# 01-AD9546-Main.net
KiCad netlist of a schematic drawn in Altium Designer
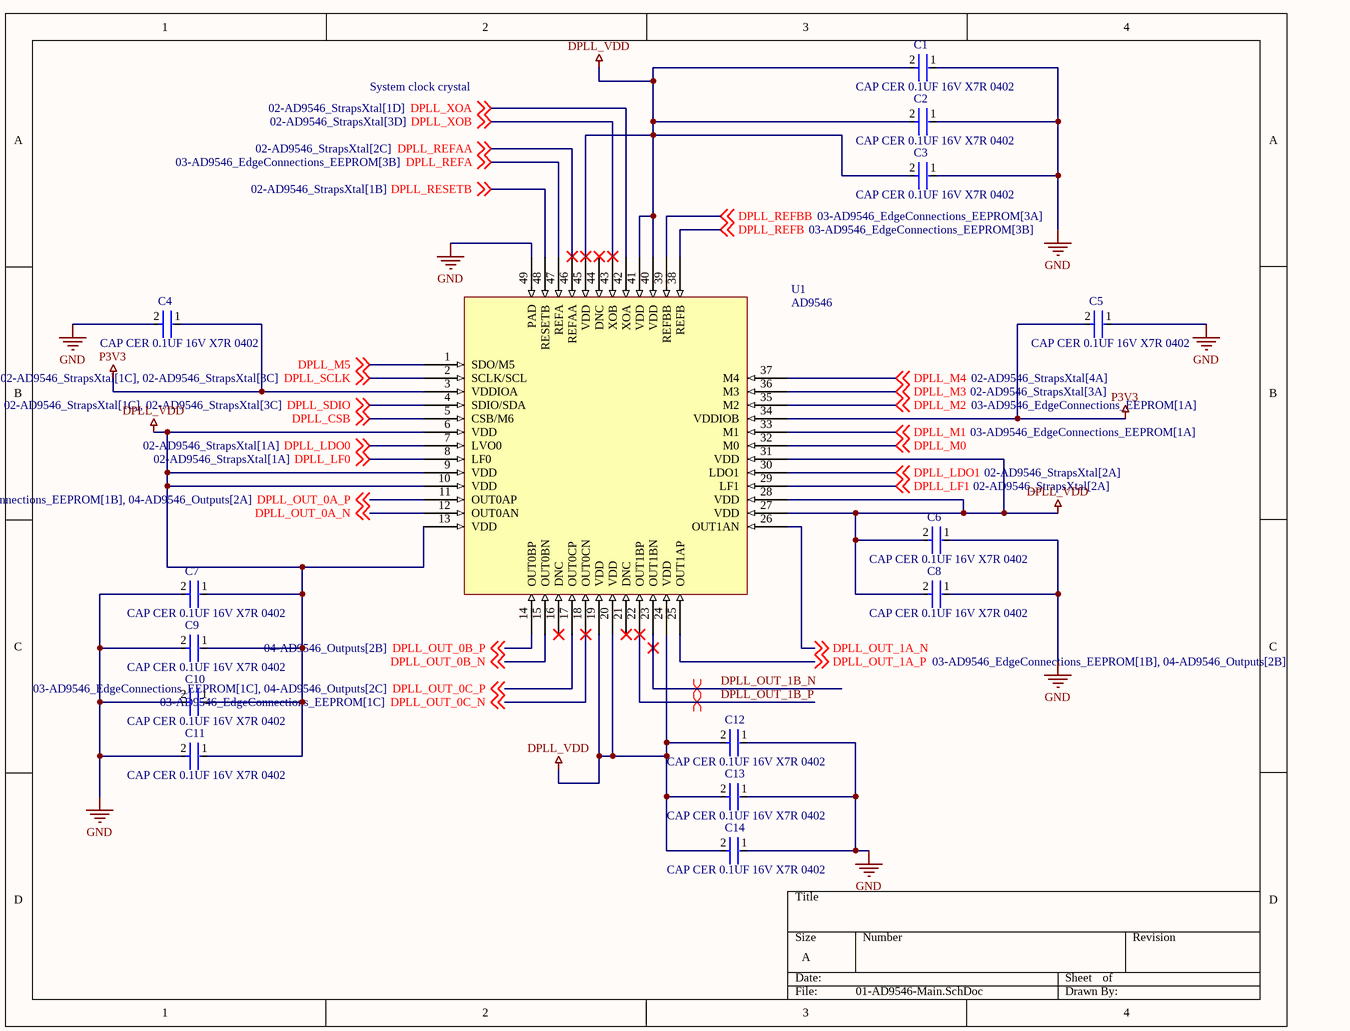
[diagram p0: 01-AD9546-Main.SchDoc]

(export (version "E")
  (design (tool "Eeschema 10.0.6"))
  (components
    (comp (ref "C1")
      (value "GRM155R71C104KA88D")
      (footprint "FP-GRM15-MFG")
      (description "CAP CER 0.1UF 16V X7R 0402")
      (fields
        (field (name "TOLERANCE") "10%")
        (field (name "OCTOPART") "https://octopart.com/grm155r71c104ka88d-murata-196880")
        (field (name "DIGIKEY DESCRIPTION") "CAP CER 0.1UF 16V X7R 0402")
      )
      (libsource (lib "Altium Content Vault") (part "236180d848d6139a670b325ea6854c9"))
    )
    (comp (ref "C2")
      (value "GRM155R71C104KA88D")
      (footprint "FP-GRM15-MFG")
      (description "CAP CER 0.1UF 16V X7R 0402")
      (fields
        (field (name "TOLERANCE") "10%")
        (field (name "OCTOPART") "https://octopart.com/grm155r71c104ka88d-murata-196880")
        (field (name "DIGIKEY DESCRIPTION") "CAP CER 0.1UF 16V X7R 0402")
      )
      (libsource (lib "Altium Content Vault") (part "236180d848d6139a670b325ea6854c9"))
    )
    (comp (ref "C3")
      (value "GRM155R71C104KA88D")
      (footprint "FP-GRM15-MFG")
      (description "CAP CER 0.1UF 16V X7R 0402")
      (fields
        (field (name "TOLERANCE") "10%")
        (field (name "OCTOPART") "https://octopart.com/grm155r71c104ka88d-murata-196880")
        (field (name "DIGIKEY DESCRIPTION") "CAP CER 0.1UF 16V X7R 0402")
      )
      (libsource (lib "Altium Content Vault") (part "236180d848d6139a670b325ea6854c9"))
    )
    (comp (ref "C4")
      (value "GRM155R71C104KA88D")
      (footprint "FP-GRM15-MFG")
      (description "CAP CER 0.1UF 16V X7R 0402")
      (fields
        (field (name "TOLERANCE") "10%")
        (field (name "OCTOPART") "https://octopart.com/grm155r71c104ka88d-murata-196880")
        (field (name "DIGIKEY DESCRIPTION") "CAP CER 0.1UF 16V X7R 0402")
      )
      (libsource (lib "Altium Content Vault") (part "236180d848d6139a670b325ea6854c9"))
    )
    (comp (ref "C5")
      (value "GRM155R71C104KA88D")
      (footprint "FP-GRM15-MFG")
      (description "CAP CER 0.1UF 16V X7R 0402")
      (fields
        (field (name "TOLERANCE") "10%")
        (field (name "OCTOPART") "https://octopart.com/grm155r71c104ka88d-murata-196880")
        (field (name "DIGIKEY DESCRIPTION") "CAP CER 0.1UF 16V X7R 0402")
      )
      (libsource (lib "Altium Content Vault") (part "236180d848d6139a670b325ea6854c9"))
    )
    (comp (ref "C6")
      (value "GRM155R71C104KA88D")
      (footprint "FP-GRM15-MFG")
      (description "CAP CER 0.1UF 16V X7R 0402")
      (fields
        (field (name "TOLERANCE") "10%")
        (field (name "OCTOPART") "https://octopart.com/grm155r71c104ka88d-murata-196880")
        (field (name "DIGIKEY DESCRIPTION") "CAP CER 0.1UF 16V X7R 0402")
      )
      (libsource (lib "Altium Content Vault") (part "236180d848d6139a670b325ea6854c9"))
    )
    (comp (ref "C7")
      (value "GRM155R71C104KA88D")
      (footprint "FP-GRM15-MFG")
      (description "CAP CER 0.1UF 16V X7R 0402")
      (fields
        (field (name "TOLERANCE") "10%")
        (field (name "OCTOPART") "https://octopart.com/grm155r71c104ka88d-murata-196880")
        (field (name "DIGIKEY DESCRIPTION") "CAP CER 0.1UF 16V X7R 0402")
      )
      (libsource (lib "Altium Content Vault") (part "236180d848d6139a670b325ea6854c9"))
    )
    (comp (ref "C8")
      (value "GRM155R71C104KA88D")
      (footprint "FP-GRM15-MFG")
      (description "CAP CER 0.1UF 16V X7R 0402")
      (fields
        (field (name "TOLERANCE") "10%")
        (field (name "OCTOPART") "https://octopart.com/grm155r71c104ka88d-murata-196880")
        (field (name "DIGIKEY DESCRIPTION") "CAP CER 0.1UF 16V X7R 0402")
      )
      (libsource (lib "Altium Content Vault") (part "236180d848d6139a670b325ea6854c9"))
    )
    (comp (ref "C9")
      (value "GRM155R71C104KA88D")
      (footprint "FP-GRM15-MFG")
      (description "CAP CER 0.1UF 16V X7R 0402")
      (fields
        (field (name "TOLERANCE") "10%")
        (field (name "OCTOPART") "https://octopart.com/grm155r71c104ka88d-murata-196880")
        (field (name "DIGIKEY DESCRIPTION") "CAP CER 0.1UF 16V X7R 0402")
      )
      (libsource (lib "Altium Content Vault") (part "236180d848d6139a670b325ea6854c9"))
    )
    (comp (ref "C10")
      (value "GRM155R71C104KA88D")
      (footprint "FP-GRM15-MFG")
      (description "CAP CER 0.1UF 16V X7R 0402")
      (fields
        (field (name "TOLERANCE") "10%")
        (field (name "OCTOPART") "https://octopart.com/grm155r71c104ka88d-murata-196880")
        (field (name "DIGIKEY DESCRIPTION") "CAP CER 0.1UF 16V X7R 0402")
      )
      (libsource (lib "Altium Content Vault") (part "236180d848d6139a670b325ea6854c9"))
    )
    (comp (ref "C11")
      (value "GRM155R71C104KA88D")
      (footprint "FP-GRM15-MFG")
      (description "CAP CER 0.1UF 16V X7R 0402")
      (fields
        (field (name "TOLERANCE") "10%")
        (field (name "OCTOPART") "https://octopart.com/grm155r71c104ka88d-murata-196880")
        (field (name "DIGIKEY DESCRIPTION") "CAP CER 0.1UF 16V X7R 0402")
      )
      (libsource (lib "Altium Content Vault") (part "236180d848d6139a670b325ea6854c9"))
    )
    (comp (ref "C12")
      (value "GRM155R71C104KA88D")
      (footprint "FP-GRM15-MFG")
      (description "CAP CER 0.1UF 16V X7R 0402")
      (fields
        (field (name "TOLERANCE") "10%")
        (field (name "OCTOPART") "https://octopart.com/grm155r71c104ka88d-murata-196880")
        (field (name "DIGIKEY DESCRIPTION") "CAP CER 0.1UF 16V X7R 0402")
      )
      (libsource (lib "Altium Content Vault") (part "236180d848d6139a670b325ea6854c9"))
    )
    (comp (ref "C13")
      (value "GRM155R71C104KA88D")
      (footprint "FP-GRM15-MFG")
      (description "CAP CER 0.1UF 16V X7R 0402")
      (fields
        (field (name "TOLERANCE") "10%")
        (field (name "OCTOPART") "https://octopart.com/grm155r71c104ka88d-murata-196880")
        (field (name "DIGIKEY DESCRIPTION") "CAP CER 0.1UF 16V X7R 0402")
      )
      (libsource (lib "Altium Content Vault") (part "236180d848d6139a670b325ea6854c9"))
    )
    (comp (ref "C14")
      (value "GRM155R71C104KA88D")
      (footprint "FP-GRM15-MFG")
      (description "CAP CER 0.1UF 16V X7R 0402")
      (fields
        (field (name "TOLERANCE") "10%")
        (field (name "OCTOPART") "https://octopart.com/grm155r71c104ka88d-murata-196880")
        (field (name "DIGIKEY DESCRIPTION") "CAP CER 0.1UF 16V X7R 0402")
      )
      (libsource (lib "Altium Content Vault") (part "236180d848d6139a670b325ea6854c9"))
    )
    (comp (ref "U1") (value "AD9546") (footprint "AD9546") (libsource (lib "TimeStick_Lib") (part "AD9546")))
  )
  (nets
    (net (code "1") (name "/DPLL_OUT_1B_N") (class "Default")
      (node (ref "U1") (pin "23") (pinfunction "OUT1BN_23") (pintype "input"))
    )
    (net (code "2") (name "/DPLL_OUT_1B_P") (class "Default")
      (node (ref "U1") (pin "22") (pinfunction "OUT1BP_22") (pintype "input+no_connect"))
    )
    (net (code "3") (name "DPLL_CSB") (class "Default")
      (node (ref "U1") (pin "5") (pinfunction "CSB/M6_5") (pintype "input"))
    )
    (net (code "4") (name "DPLL_LDO0") (class "Default")
      (node (ref "U1") (pin "7") (pinfunction "LVO0_7") (pintype "input"))
    )
    (net (code "5") (name "DPLL_LDO1") (class "Default")
      (node (ref "U1") (pin "30") (pinfunction "LDO1_30") (pintype "input"))
    )
    (net (code "6") (name "DPLL_LF0") (class "Default")
      (node (ref "U1") (pin "8") (pinfunction "LF0_8") (pintype "input"))
    )
    (net (code "7") (name "DPLL_LF1") (class "Default")
      (node (ref "U1") (pin "29") (pinfunction "LF1_29") (pintype "input"))
    )
    (net (code "8") (name "DPLL_M0") (class "Default")
      (node (ref "U1") (pin "32") (pinfunction "M0_32") (pintype "input"))
    )
    (net (code "9") (name "DPLL_M1") (class "Default")
      (node (ref "U1") (pin "33") (pinfunction "M1_33") (pintype "input"))
    )
    (net (code "10") (name "DPLL_M2") (class "Default")
      (node (ref "U1") (pin "35") (pinfunction "M2_35") (pintype "input"))
    )
    (net (code "11") (name "DPLL_M3") (class "Default")
      (node (ref "U1") (pin "36") (pinfunction "M3_36") (pintype "input"))
    )
    (net (code "12") (name "DPLL_M4") (class "Default")
      (node (ref "U1") (pin "37") (pinfunction "M4_37") (pintype "input"))
    )
    (net (code "13") (name "DPLL_M5") (class "Default")
      (node (ref "U1") (pin "1") (pinfunction "SDO/M5_1") (pintype "input"))
    )
    (net (code "14") (name "DPLL_OUT_0A_N") (class "Default")
      (node (ref "U1") (pin "12") (pinfunction "OUT0AN_12") (pintype "input"))
    )
    (net (code "15") (name "DPLL_OUT_0A_P") (class "Default")
      (node (ref "U1") (pin "11") (pinfunction "OUT0AP_11") (pintype "input"))
    )
    (net (code "16") (name "DPLL_OUT_0B_N") (class "Default")
      (node (ref "U1") (pin "15") (pinfunction "OUT0BN_15") (pintype "input"))
    )
    (net (code "17") (name "DPLL_OUT_0B_P") (class "Default")
      (node (ref "U1") (pin "14") (pinfunction "OUT0BP_14") (pintype "input"))
    )
    (net (code "18") (name "DPLL_OUT_0C_N") (class "Default")
      (node (ref "U1") (pin "18") (pinfunction "OUT0CN_18") (pintype "input"))
    )
    (net (code "19") (name "DPLL_OUT_0C_P") (class "Default")
      (node (ref "U1") (pin "17") (pinfunction "OUT0CP_17") (pintype "input"))
    )
    (net (code "20") (name "DPLL_OUT_1A_N") (class "Default")
      (node (ref "U1") (pin "26") (pinfunction "OUT1AN_26") (pintype "input"))
    )
    (net (code "21") (name "DPLL_OUT_1A_P") (class "Default")
      (node (ref "U1") (pin "25") (pinfunction "OUT1AP_25") (pintype "input"))
    )
    (net (code "22") (name "DPLL_REFA") (class "Default")
      (node (ref "U1") (pin "47") (pinfunction "REFA_47") (pintype "input"))
    )
    (net (code "23") (name "DPLL_REFAA") (class "Default")
      (node (ref "U1") (pin "46") (pinfunction "REFAA_46") (pintype "input"))
    )
    (net (code "24") (name "DPLL_REFB") (class "Default")
      (node (ref "U1") (pin "38") (pinfunction "REFB_38") (pintype "input"))
    )
    (net (code "25") (name "DPLL_REFBB") (class "Default")
      (node (ref "U1") (pin "39") (pinfunction "REFBB_39") (pintype "input"))
    )
    (net (code "26") (name "DPLL_RESETB") (class "Default")
      (node (ref "U1") (pin "48") (pinfunction "RESETB_48") (pintype "input"))
    )
    (net (code "27") (name "DPLL_SCLK") (class "Default")
      (node (ref "U1") (pin "2") (pinfunction "SCLK/SCL_2") (pintype "input"))
    )
    (net (code "28") (name "DPLL_SDIO") (class "Default")
      (node (ref "U1") (pin "4") (pinfunction "SDIO/SDA_4") (pintype "input"))
    )
    (net (code "29") (name "DPLL_VDD") (class "Default")
      (node (ref "C1") (pin "2") (pinfunction "2_2") (pintype "passive"))
      (node (ref "C10") (pin "1") (pinfunction "1_1") (pintype "passive"))
      (node (ref "C11") (pin "1") (pinfunction "1_1") (pintype "passive"))
      (node (ref "C12") (pin "2") (pinfunction "2_2") (pintype "passive"))
      (node (ref "C13") (pin "2") (pinfunction "2_2") (pintype "passive"))
      (node (ref "C14") (pin "2") (pinfunction "2_2") (pintype "passive"))
      (node (ref "C2") (pin "2") (pinfunction "2_2") (pintype "passive"))
      (node (ref "C3") (pin "2") (pinfunction "2_2") (pintype "passive"))
      (node (ref "C6") (pin "2") (pinfunction "2_2") (pintype "passive"))
      (node (ref "C7") (pin "1") (pinfunction "1_1") (pintype "passive"))
      (node (ref "C8") (pin "2") (pinfunction "2_2") (pintype "passive"))
      (node (ref "C9") (pin "1") (pinfunction "1_1") (pintype "passive"))
      (node (ref "U1") (pin "10") (pinfunction "VDD_10") (pintype "input"))
      (node (ref "U1") (pin "13") (pinfunction "VDD_13") (pintype "input"))
      (node (ref "U1") (pin "19") (pinfunction "VDD_19") (pintype "input"))
      (node (ref "U1") (pin "20") (pinfunction "VDD_20") (pintype "input"))
      (node (ref "U1") (pin "24") (pinfunction "VDD_24") (pintype "input"))
      (node (ref "U1") (pin "27") (pinfunction "VDD_27") (pintype "input"))
      (node (ref "U1") (pin "28") (pinfunction "VDD_28") (pintype "input"))
      (node (ref "U1") (pin "31") (pinfunction "VDD_31") (pintype "input"))
      (node (ref "U1") (pin "40") (pinfunction "VDD_40") (pintype "input"))
      (node (ref "U1") (pin "41") (pinfunction "VDD_41") (pintype "input"))
      (node (ref "U1") (pin "45") (pinfunction "VDD_45") (pintype "input"))
      (node (ref "U1") (pin "6") (pinfunction "VDD_6") (pintype "input"))
      (node (ref "U1") (pin "9") (pinfunction "VDD_9") (pintype "input"))
    )
    (net (code "30") (name "DPLL_XOA") (class "Default")
      (node (ref "U1") (pin "42") (pinfunction "XOA_42") (pintype "input"))
    )
    (net (code "31") (name "DPLL_XOB") (class "Default")
      (node (ref "U1") (pin "43") (pinfunction "XOB_43") (pintype "input"))
    )
    (net (code "32") (name "GND") (class "Default")
      (node (ref "C1") (pin "1") (pinfunction "1_1") (pintype "passive"))
      (node (ref "C10") (pin "2") (pinfunction "2_2") (pintype "passive"))
      (node (ref "C11") (pin "2") (pinfunction "2_2") (pintype "passive"))
      (node (ref "C12") (pin "1") (pinfunction "1_1") (pintype "passive"))
      (node (ref "C13") (pin "1") (pinfunction "1_1") (pintype "passive"))
      (node (ref "C14") (pin "1") (pinfunction "1_1") (pintype "passive"))
      (node (ref "C2") (pin "1") (pinfunction "1_1") (pintype "passive"))
      (node (ref "C3") (pin "1") (pinfunction "1_1") (pintype "passive"))
      (node (ref "C4") (pin "2") (pinfunction "2_2") (pintype "passive"))
      (node (ref "C5") (pin "1") (pinfunction "1_1") (pintype "passive"))
      (node (ref "C6") (pin "1") (pinfunction "1_1") (pintype "passive"))
      (node (ref "C7") (pin "2") (pinfunction "2_2") (pintype "passive"))
      (node (ref "C8") (pin "1") (pinfunction "1_1") (pintype "passive"))
      (node (ref "C9") (pin "2") (pinfunction "2_2") (pintype "passive"))
      (node (ref "U1") (pin "49") (pinfunction "PAD_49") (pintype "input"))
    )
    (net (code "33") (name "P3V3") (class "Default")
      (node (ref "C4") (pin "1") (pinfunction "1_1") (pintype "passive"))
      (node (ref "C5") (pin "2") (pinfunction "2_2") (pintype "passive"))
      (node (ref "U1") (pin "3") (pinfunction "VDDIOA_3") (pintype "input"))
      (node (ref "U1") (pin "34") (pinfunction "VDDIOB_34") (pintype "input"))
    )
    (net (code "34") (name "unconnected-(U1-DNC-Pad16)") (class "Default")
      (node (ref "U1") (pin "16") (pinfunction "DNC_16") (pintype "input+no_connect"))
    )
    (net (code "35") (name "unconnected-(U1-DNC-Pad21)") (class "Default")
      (node (ref "U1") (pin "21") (pinfunction "DNC_21") (pintype "input+no_connect"))
    )
    (net (code "36") (name "unconnected-(U1-DNC-Pad44)") (class "Default")
      (node (ref "U1") (pin "44") (pinfunction "DNC_44") (pintype "input+no_connect"))
    )
  )
)
